# cardV3.net
KiCad netlist of a schematic drawn in EAGLE
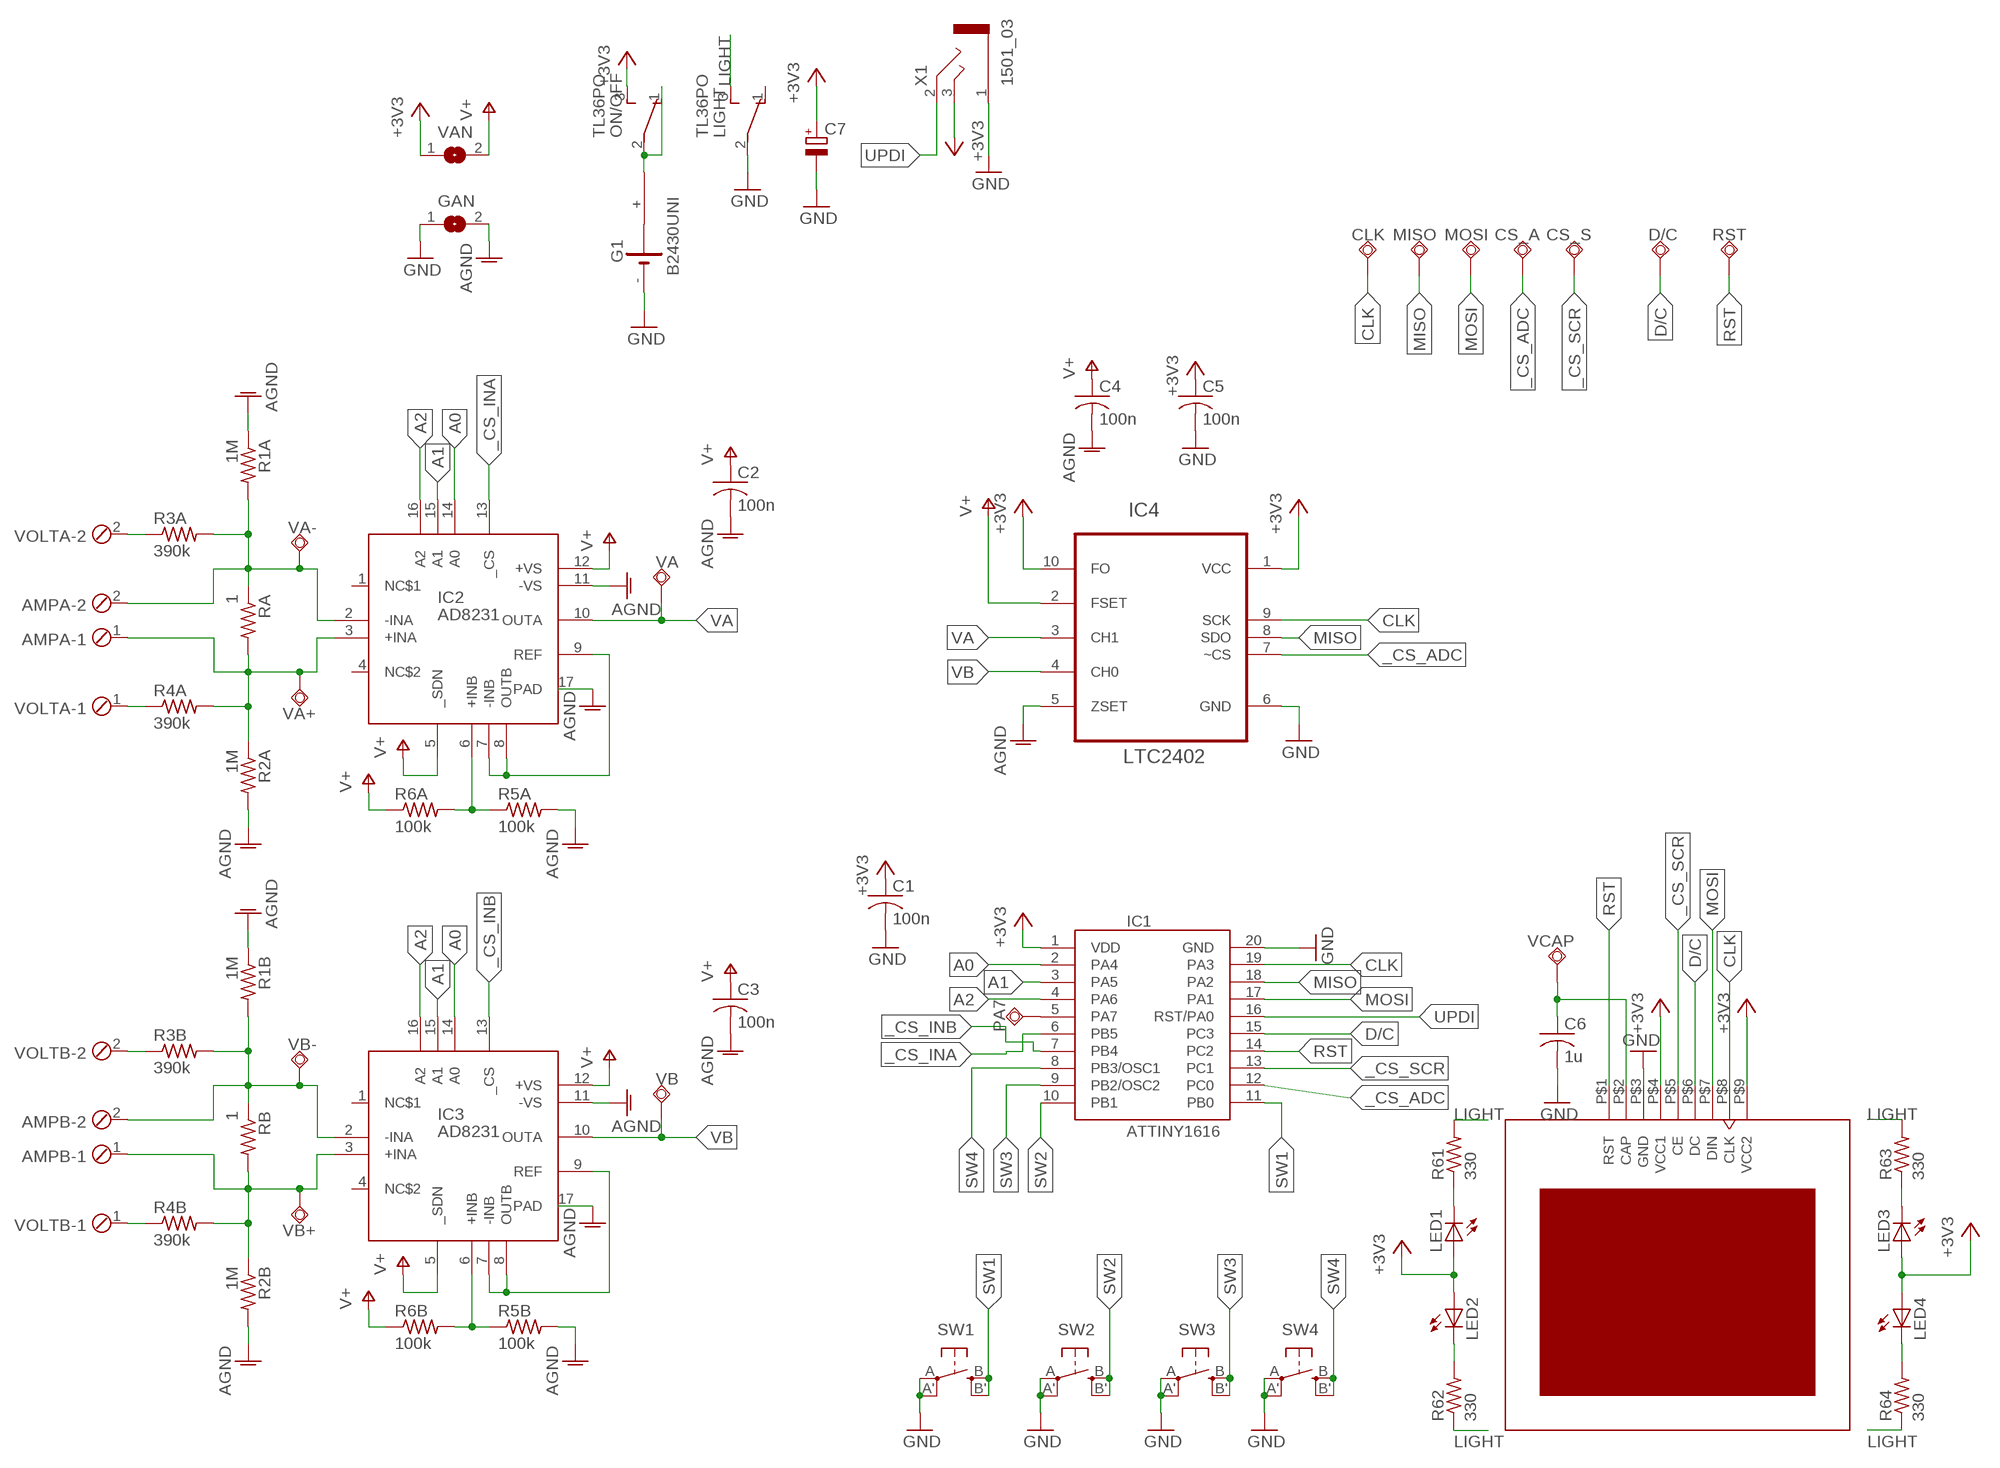
[diagram p0: schematic, sheet 1]

(export (version "E")
  (design (tool "Eeschema 10.0.6"))
  (components
    (comp (ref "AMPA")
      (value "MPT2")
      (footprint "eagle-import:2POL254")
      (libsource (lib "eagle-import") (part "MPT2"))
    )
    (comp (ref "AMPB")
      (value "MPT2")
      (footprint "eagle-import:2POL254")
      (libsource (lib "eagle-import") (part "MPT2"))
    )
    (comp (ref "C1")
      (value "100n")
      (footprint "eagle-import:C0805K")
      (libsource (lib "eagle-import") (part "C-USC0805K"))
    )
    (comp (ref "C2")
      (value "100n")
      (footprint "eagle-import:C0805K")
      (libsource (lib "eagle-import") (part "C-USC0805K"))
    )
    (comp (ref "C3")
      (value "100n")
      (footprint "eagle-import:C0805K")
      (libsource (lib "eagle-import") (part "C-USC0805K"))
    )
    (comp (ref "C4")
      (value "100n")
      (footprint "eagle-import:C0805K")
      (libsource (lib "eagle-import") (part "C-USC0805K"))
    )
    (comp (ref "C5")
      (value "100n")
      (footprint "eagle-import:C0805K")
      (libsource (lib "eagle-import") (part "C-USC0805K"))
    )
    (comp (ref "C6")
      (value "1u")
      (footprint "eagle-import:C0805")
      (libsource (lib "eagle-import") (part "resistor_C-USC0805"))
    )
    (comp (ref "C7")
      (value "CPOL-EU153CLV-0405")
      (footprint "eagle-import:153CLV-0405")
      (libsource (lib "eagle-import") (part "CPOL-EU153CLV-0405"))
    )
    (comp (ref "CLK")
      (value "TPSQB1,27")
      (footprint "eagle-import:B1,27")
      (libsource (lib "eagle-import") (part "TPSQB1,27"))
    )
    (comp (ref "CS_A")
      (value "TPSQB1,27")
      (footprint "eagle-import:B1,27")
      (libsource (lib "eagle-import") (part "TPSQB1,27"))
    )
    (comp (ref "CS_S")
      (value "TPSQB1,27")
      (footprint "eagle-import:B1,27")
      (libsource (lib "eagle-import") (part "TPSQB1,27"))
    )
    (comp (ref "D/C")
      (value "TPSQB1,27")
      (footprint "eagle-import:B1,27")
      (libsource (lib "eagle-import") (part "TPSQB1,27"))
    )
    (comp (ref "G1")
      (value "B2430UNI")
      (footprint "eagle-import:B2430UNI")
      (libsource (lib "eagle-import") (part "B2430UNI"))
    )
    (comp (ref "GAN") (value "SJ") (footprint "eagle-import:SJ") (libsource (lib "eagle-import") (part "SJ")))
    (comp (ref "IC1")
      (value "ATTINY1616")
      (footprint "eagle-import:SO20W")
      (libsource (lib "eagle-import") (part "ATTINY1616"))
    )
    (comp (ref "IC2")
      (value "AD8231")
      (footprint "eagle-import:LFCSP16")
      (libsource (lib "eagle-import") (part "AD8231"))
    )
    (comp (ref "IC3")
      (value "AD8231")
      (footprint "eagle-import:LFCSP16")
      (libsource (lib "eagle-import") (part "AD8231"))
    )
    (comp (ref "IC4")
      (value "LTC2402")
      (footprint "eagle-import:MSOP10")
      (libsource (lib "eagle-import") (part "LTC2402CMS"))
    )
    (comp (ref "LED1")
      (value "LEDCHIP-LED0805")
      (footprint "eagle-import:CHIP-LED0805")
      (libsource (lib "eagle-import") (part "LEDCHIP-LED0805"))
    )
    (comp (ref "LED2")
      (value "LEDCHIP-LED0805")
      (footprint "eagle-import:CHIP-LED0805")
      (libsource (lib "eagle-import") (part "LEDCHIP-LED0805"))
    )
    (comp (ref "LED3")
      (value "LEDCHIP-LED0805")
      (footprint "eagle-import:CHIP-LED0805")
      (libsource (lib "eagle-import") (part "LEDCHIP-LED0805"))
    )
    (comp (ref "LED4")
      (value "LEDCHIP-LED0805")
      (footprint "eagle-import:CHIP-LED0805")
      (libsource (lib "eagle-import") (part "LEDCHIP-LED0805"))
    )
    (comp (ref "LIGHT")
      (value "TL36PO")
      (footprint "eagle-import:TL3XPO")
      (libsource (lib "eagle-import") (part "TL36PO"))
    )
    (comp (ref "MISO")
      (value "TPSQB1,27")
      (footprint "eagle-import:B1,27")
      (libsource (lib "eagle-import") (part "TPSQB1,27"))
    )
    (comp (ref "MOSI")
      (value "TPSQB1,27")
      (footprint "eagle-import:B1,27")
      (libsource (lib "eagle-import") (part "TPSQB1,27"))
    )
    (comp (ref "ON/OFF")
      (value "TL36PO")
      (footprint "eagle-import:TL3XPO")
      (libsource (lib "eagle-import") (part "TL36PO"))
    )
    (comp (ref "PA7")
      (value "TPSQB1,27")
      (footprint "eagle-import:B1,27")
      (libsource (lib "eagle-import") (part "TPSQB1,27"))
    )
    (comp (ref "R1A")
      (value "1M")
      (footprint "eagle-import:M0805")
      (libsource (lib "eagle-import") (part "R-US_M0805"))
    )
    (comp (ref "R1B")
      (value "1M")
      (footprint "eagle-import:M0805")
      (libsource (lib "eagle-import") (part "R-US_M0805"))
    )
    (comp (ref "R2A")
      (value "1M")
      (footprint "eagle-import:M0805")
      (libsource (lib "eagle-import") (part "R-US_M0805"))
    )
    (comp (ref "R2B")
      (value "1M")
      (footprint "eagle-import:M0805")
      (libsource (lib "eagle-import") (part "R-US_M0805"))
    )
    (comp (ref "R3A")
      (value "390k")
      (footprint "eagle-import:M0805")
      (libsource (lib "eagle-import") (part "R-US_M0805"))
    )
    (comp (ref "R3B")
      (value "390k")
      (footprint "eagle-import:M0805")
      (libsource (lib "eagle-import") (part "R-US_M0805"))
    )
    (comp (ref "R4A")
      (value "390k")
      (footprint "eagle-import:M0805")
      (libsource (lib "eagle-import") (part "R-US_M0805"))
    )
    (comp (ref "R4B")
      (value "390k")
      (footprint "eagle-import:M0805")
      (libsource (lib "eagle-import") (part "R-US_M0805"))
    )
    (comp (ref "R5A")
      (value "100k")
      (footprint "eagle-import:M0805")
      (libsource (lib "eagle-import") (part "R-US_M0805"))
    )
    (comp (ref "R5B")
      (value "100k")
      (footprint "eagle-import:M0805")
      (libsource (lib "eagle-import") (part "R-US_M0805"))
    )
    (comp (ref "R6A")
      (value "100k")
      (footprint "eagle-import:M0805")
      (libsource (lib "eagle-import") (part "R-US_M0805"))
    )
    (comp (ref "R6B")
      (value "100k")
      (footprint "eagle-import:M0805")
      (libsource (lib "eagle-import") (part "R-US_M0805"))
    )
    (comp (ref "R61")
      (value "330")
      (footprint "eagle-import:M0805")
      (libsource (lib "eagle-import") (part "R-US_M0805"))
    )
    (comp (ref "R62")
      (value "330")
      (footprint "eagle-import:M0805")
      (libsource (lib "eagle-import") (part "R-US_M0805"))
    )
    (comp (ref "R63")
      (value "330")
      (footprint "eagle-import:M0805")
      (libsource (lib "eagle-import") (part "R-US_M0805"))
    )
    (comp (ref "R64")
      (value "330")
      (footprint "eagle-import:M0805")
      (libsource (lib "eagle-import") (part "R-US_M0805"))
    )
    (comp (ref "RA")
      (value "1")
      (footprint "eagle-import:M0805")
      (libsource (lib "eagle-import") (part "R-US_M0805"))
    )
    (comp (ref "RB")
      (value "1")
      (footprint "eagle-import:M0805")
      (libsource (lib "eagle-import") (part "R-US_M0805"))
    )
    (comp (ref "RST")
      (value "TPSQB1,27")
      (footprint "eagle-import:B1,27")
      (libsource (lib "eagle-import") (part "TPSQB1,27"))
    )
    (comp (ref "SCR")
      (value "NOKIA_SCREEN")
      (footprint "eagle-import:NOKIA_SCREEN")
      (libsource (lib "eagle-import") (part "NOKIA_SCREEN"))
    )
    (comp (ref "SW1")
      (value "SPST_TACT-EVQQ2")
      (footprint "eagle-import:EVQ-Q2")
      (libsource (lib "eagle-import") (part "SPST_TACT-EVQQ2"))
    )
    (comp (ref "SW2")
      (value "SPST_TACT-EVQQ2")
      (footprint "eagle-import:EVQ-Q2")
      (libsource (lib "eagle-import") (part "SPST_TACT-EVQQ2"))
    )
    (comp (ref "SW3")
      (value "SPST_TACT-EVQQ2")
      (footprint "eagle-import:EVQ-Q2")
      (libsource (lib "eagle-import") (part "SPST_TACT-EVQQ2"))
    )
    (comp (ref "SW4")
      (value "SPST_TACT-EVQQ2")
      (footprint "eagle-import:EVQ-Q2")
      (libsource (lib "eagle-import") (part "SPST_TACT-EVQQ2"))
    )
    (comp (ref "VA")
      (value "TPSQB1,27")
      (footprint "eagle-import:B1,27")
      (libsource (lib "eagle-import") (part "TPSQB1,27"))
    )
    (comp (ref "VA+")
      (value "TPSQB1,27")
      (footprint "eagle-import:B1,27")
      (libsource (lib "eagle-import") (part "TPSQB1,27"))
    )
    (comp (ref "VA-")
      (value "TPSQB1,27")
      (footprint "eagle-import:B1,27")
      (libsource (lib "eagle-import") (part "TPSQB1,27"))
    )
    (comp (ref "VAN") (value "SJ") (footprint "eagle-import:SJ") (libsource (lib "eagle-import") (part "SJ")))
    (comp (ref "VB")
      (value "TPSQB1,27")
      (footprint "eagle-import:B1,27")
      (libsource (lib "eagle-import") (part "TPSQB1,27"))
    )
    (comp (ref "VB+")
      (value "TPSQB1,27")
      (footprint "eagle-import:B1,27")
      (libsource (lib "eagle-import") (part "TPSQB1,27"))
    )
    (comp (ref "VB-")
      (value "TPSQB1,27")
      (footprint "eagle-import:B1,27")
      (libsource (lib "eagle-import") (part "TPSQB1,27"))
    )
    (comp (ref "VCAP")
      (value "TPSQB1,27")
      (footprint "eagle-import:B1,27")
      (libsource (lib "eagle-import") (part "TPSQB1,27"))
    )
    (comp (ref "VOLTA")
      (value "MPT2")
      (footprint "eagle-import:2POL254")
      (libsource (lib "eagle-import") (part "MPT2"))
    )
    (comp (ref "VOLTB")
      (value "MPT2")
      (footprint "eagle-import:2POL254")
      (libsource (lib "eagle-import") (part "MPT2"))
    )
    (comp (ref "X1")
      (value "1501_03")
      (footprint "eagle-import:1501_03")
      (libsource (lib "eagle-import") (part "1501_03"))
    )
  )
  (nets
    (net (code "1") (name "+3V3") (class "Default")
      (node (ref "C1") (pin "1") (pinfunction "1_1") (pintype "passive"))
      (node (ref "C5") (pin "1") (pinfunction "1_1") (pintype "passive"))
      (node (ref "C7") (pin "+") (pinfunction "+_+") (pintype "passive"))
      (node (ref "IC1") (pin "1") (pinfunction "VDD_1") (pintype "power_in"))
      (node (ref "IC4") (pin "1") (pinfunction "VCC_1") (pintype "power_in"))
      (node (ref "IC4") (pin "10") (pinfunction "FO_10") (pintype "input"))
      (node (ref "LED1") (pin "A") (pinfunction "A_A") (pintype "passive"))
      (node (ref "LED2") (pin "A") (pinfunction "A_A") (pintype "passive"))
      (node (ref "LED3") (pin "A") (pinfunction "A_A") (pintype "passive"))
      (node (ref "LED4") (pin "A") (pinfunction "A_A") (pintype "passive"))
      (node (ref "ON/OFF") (pin "3") (pinfunction "S_3") (pintype "passive"))
      (node (ref "SCR") (pin "P$4") (pinfunction "VCC1_P$4") (pintype "power_in"))
      (node (ref "SCR") (pin "P$9") (pinfunction "VCC2_P$9") (pintype "power_in"))
      (node (ref "VAN") (pin "1") (pinfunction "1_1") (pintype "passive"))
      (node (ref "X1") (pin "3") (pinfunction "3_3") (pintype "passive"))
    )
    (net (code "2") (name "/LIGHT") (class "Default")
      (node (ref "LIGHT") (pin "3") (pinfunction "S_3") (pintype "passive"))
      (node (ref "R61") (pin "2") (pinfunction "2_2") (pintype "passive"))
      (node (ref "R62") (pin "1") (pinfunction "1_1") (pintype "passive"))
      (node (ref "R63") (pin "2") (pinfunction "2_2") (pintype "passive"))
      (node (ref "R64") (pin "1") (pinfunction "1_1") (pintype "passive"))
    )
    (net (code "3") (name "A0") (class "Default")
      (node (ref "IC1") (pin "2") (pinfunction "PA4_2") (pintype "bidirectional"))
      (node (ref "IC2") (pin "14") (pinfunction "A0_14") (pintype "input"))
      (node (ref "IC3") (pin "14") (pinfunction "A0_14") (pintype "input"))
    )
    (net (code "4") (name "A1") (class "Default")
      (node (ref "IC1") (pin "3") (pinfunction "PA5_3") (pintype "bidirectional"))
      (node (ref "IC2") (pin "15") (pinfunction "A1_15") (pintype "input"))
      (node (ref "IC3") (pin "15") (pinfunction "A1_15") (pintype "input"))
    )
    (net (code "5") (name "A2") (class "Default")
      (node (ref "IC1") (pin "4") (pinfunction "PA6_4") (pintype "bidirectional"))
      (node (ref "IC2") (pin "16") (pinfunction "A2_16") (pintype "input"))
      (node (ref "IC3") (pin "16") (pinfunction "A2_16") (pintype "input"))
    )
    (net (code "6") (name "AGND") (class "Default")
      (node (ref "C2") (pin "2") (pinfunction "2_2") (pintype "passive"))
      (node (ref "C3") (pin "2") (pinfunction "2_2") (pintype "passive"))
      (node (ref "C4") (pin "2") (pinfunction "2_2") (pintype "passive"))
      (node (ref "GAN") (pin "2") (pinfunction "2_2") (pintype "passive"))
      (node (ref "IC2") (pin "11") (pinfunction "-VS_11") (pintype "power_in"))
      (node (ref "IC2") (pin "17") (pinfunction "PAD_17") (pintype "power_in"))
      (node (ref "IC3") (pin "11") (pinfunction "-VS_11") (pintype "power_in"))
      (node (ref "IC3") (pin "17") (pinfunction "PAD_17") (pintype "power_in"))
      (node (ref "IC4") (pin "5") (pinfunction "ZSET_5") (pintype "input"))
      (node (ref "R1A") (pin "1") (pinfunction "1_1") (pintype "passive"))
      (node (ref "R1B") (pin "1") (pinfunction "1_1") (pintype "passive"))
      (node (ref "R2A") (pin "2") (pinfunction "2_2") (pintype "passive"))
      (node (ref "R2B") (pin "2") (pinfunction "2_2") (pintype "passive"))
      (node (ref "R5A") (pin "2") (pinfunction "2_2") (pintype "passive"))
      (node (ref "R5B") (pin "2") (pinfunction "2_2") (pintype "passive"))
    )
    (net (code "7") (name "CLK") (class "Default")
      (node (ref "CLK") (pin "TP") (pinfunction "TP_TP") (pintype "input"))
      (node (ref "IC1") (pin "19") (pinfunction "PA3_19") (pintype "bidirectional"))
      (node (ref "IC4") (pin "9") (pinfunction "SCK_9") (pintype "input"))
      (node (ref "SCR") (pin "P$8") (pinfunction "CLK_P$8") (pintype "input"))
    )
    (net (code "8") (name "D{slash}C") (class "Default")
      (node (ref "D/C") (pin "TP") (pinfunction "TP_TP") (pintype "input"))
      (node (ref "IC1") (pin "15") (pinfunction "PC3_15") (pintype "bidirectional"))
      (node (ref "SCR") (pin "P$6") (pinfunction "DC_P$6") (pintype "input"))
    )
    (net (code "9") (name "GND") (class "Default")
      (node (ref "C1") (pin "2") (pinfunction "2_2") (pintype "passive"))
      (node (ref "C5") (pin "2") (pinfunction "2_2") (pintype "passive"))
      (node (ref "C6") (pin "2") (pinfunction "2_2") (pintype "passive"))
      (node (ref "C7") (pin "-") (pinfunction "-_-") (pintype "passive"))
      (node (ref "G1") (pin "-") (pinfunction "-_-") (pintype "passive"))
      (node (ref "GAN") (pin "1") (pinfunction "1_1") (pintype "passive"))
      (node (ref "IC1") (pin "20") (pinfunction "GND_20") (pintype "power_in"))
      (node (ref "IC4") (pin "6") (pinfunction "GND_6") (pintype "passive"))
      (node (ref "LIGHT") (pin "2") (pinfunction "P_2") (pintype "passive"))
      (node (ref "SCR") (pin "P$3") (pinfunction "GND_P$3") (pintype "power_in"))
      (node (ref "SW1") (pin "A") (pinfunction "P_A") (pintype "passive"))
      (node (ref "SW1") (pin "A'") (pinfunction "P1_A'") (pintype "passive"))
      (node (ref "SW2") (pin "A") (pinfunction "P_A") (pintype "passive"))
      (node (ref "SW2") (pin "A'") (pinfunction "P1_A'") (pintype "passive"))
      (node (ref "SW3") (pin "A") (pinfunction "P_A") (pintype "passive"))
      (node (ref "SW3") (pin "A'") (pinfunction "P1_A'") (pintype "passive"))
      (node (ref "SW4") (pin "A") (pinfunction "P_A") (pintype "passive"))
      (node (ref "SW4") (pin "A'") (pinfunction "P1_A'") (pintype "passive"))
      (node (ref "X1") (pin "1") (pinfunction "1_1") (pintype "passive"))
    )
    (net (code "10") (name "MISO") (class "Default")
      (node (ref "IC1") (pin "18") (pinfunction "PA2_18") (pintype "bidirectional"))
      (node (ref "IC4") (pin "8") (pinfunction "SDO_8") (pintype "output"))
      (node (ref "MISO") (pin "TP") (pinfunction "TP_TP") (pintype "input"))
    )
    (net (code "11") (name "MOSI") (class "Default")
      (node (ref "IC1") (pin "17") (pinfunction "PA1_17") (pintype "bidirectional"))
      (node (ref "MOSI") (pin "TP") (pinfunction "TP_TP") (pintype "input"))
      (node (ref "SCR") (pin "P$7") (pinfunction "DIN_P$7") (pintype "input"))
    )
    (net (code "12") (name "Net-(AMPAB-1)") (class "Default")
      (node (ref "AMPA") (pin "2") (pinfunction "1_2") (pintype "passive"))
      (node (ref "IC2") (pin "2") (pinfunction "-INA_2") (pintype "input"))
      (node (ref "R1A") (pin "2") (pinfunction "2_2") (pintype "passive"))
      (node (ref "R3A") (pin "2") (pinfunction "2_2") (pintype "passive"))
      (node (ref "RA") (pin "1") (pinfunction "1_1") (pintype "passive"))
      (node (ref "VA-") (pin "TP") (pinfunction "TP_TP") (pintype "input"))
    )
    (net (code "13") (name "Net-(AMPBB-1)") (class "Default")
      (node (ref "AMPB") (pin "2") (pinfunction "1_2") (pintype "passive"))
      (node (ref "IC3") (pin "2") (pinfunction "-INA_2") (pintype "input"))
      (node (ref "R1B") (pin "2") (pinfunction "2_2") (pintype "passive"))
      (node (ref "R3B") (pin "2") (pinfunction "2_2") (pintype "passive"))
      (node (ref "RB") (pin "1") (pinfunction "1_1") (pintype "passive"))
      (node (ref "VB-") (pin "TP") (pinfunction "TP_TP") (pintype "input"))
    )
    (net (code "14") (name "Net-(IC1-PA7)") (class "Default")
      (node (ref "IC1") (pin "5") (pinfunction "PA7_5") (pintype "bidirectional"))
      (node (ref "PA7") (pin "TP") (pinfunction "TP_TP") (pintype "input"))
    )
    (net (code "15") (name "Net-(IC2-+INA)") (class "Default")
      (node (ref "AMPA") (pin "1") (pinfunction "1_1") (pintype "passive"))
      (node (ref "IC2") (pin "3") (pinfunction "+INA_3") (pintype "input"))
      (node (ref "R2A") (pin "1") (pinfunction "1_1") (pintype "passive"))
      (node (ref "R4A") (pin "2") (pinfunction "2_2") (pintype "passive"))
      (node (ref "RA") (pin "2") (pinfunction "2_2") (pintype "passive"))
      (node (ref "VA+") (pin "TP") (pinfunction "TP_TP") (pintype "input"))
    )
    (net (code "16") (name "Net-(IC2-+INB)") (class "Default")
      (node (ref "IC2") (pin "6") (pinfunction "+INB_6") (pintype "input"))
      (node (ref "R5A") (pin "1") (pinfunction "1_1") (pintype "passive"))
      (node (ref "R6A") (pin "2") (pinfunction "2_2") (pintype "passive"))
    )
    (net (code "17") (name "Net-(IC2--INB)") (class "Default")
      (node (ref "IC2") (pin "7") (pinfunction "-INB_7") (pintype "input"))
      (node (ref "IC2") (pin "8") (pinfunction "OUTB_8") (pintype "output"))
      (node (ref "IC2") (pin "9") (pinfunction "REF_9") (pintype "input"))
    )
    (net (code "18") (name "Net-(IC3-+INA)") (class "Default")
      (node (ref "AMPB") (pin "1") (pinfunction "1_1") (pintype "passive"))
      (node (ref "IC3") (pin "3") (pinfunction "+INA_3") (pintype "input"))
      (node (ref "R2B") (pin "1") (pinfunction "1_1") (pintype "passive"))
      (node (ref "R4B") (pin "2") (pinfunction "2_2") (pintype "passive"))
      (node (ref "RB") (pin "2") (pinfunction "2_2") (pintype "passive"))
      (node (ref "VB+") (pin "TP") (pinfunction "TP_TP") (pintype "input"))
    )
    (net (code "19") (name "Net-(IC3-+INB)") (class "Default")
      (node (ref "IC3") (pin "6") (pinfunction "+INB_6") (pintype "input"))
      (node (ref "R5B") (pin "1") (pinfunction "1_1") (pintype "passive"))
      (node (ref "R6B") (pin "2") (pinfunction "2_2") (pintype "passive"))
    )
    (net (code "20") (name "Net-(IC3--INB)") (class "Default")
      (node (ref "IC3") (pin "7") (pinfunction "-INB_7") (pintype "input"))
      (node (ref "IC3") (pin "8") (pinfunction "OUTB_8") (pintype "output"))
      (node (ref "IC3") (pin "9") (pinfunction "REF_9") (pintype "input"))
    )
    (net (code "21") (name "Net-(LED1-PadC)") (class "Default")
      (node (ref "LED1") (pin "C") (pinfunction "C_C") (pintype "passive"))
      (node (ref "R61") (pin "1") (pinfunction "1_1") (pintype "passive"))
    )
    (net (code "22") (name "Net-(LED2-PadC)") (class "Default")
      (node (ref "LED2") (pin "C") (pinfunction "C_C") (pintype "passive"))
      (node (ref "R62") (pin "2") (pinfunction "2_2") (pintype "passive"))
    )
    (net (code "23") (name "Net-(LED3-PadC)") (class "Default")
      (node (ref "LED3") (pin "C") (pinfunction "C_C") (pintype "passive"))
      (node (ref "R63") (pin "1") (pinfunction "1_1") (pintype "passive"))
    )
    (net (code "24") (name "Net-(LED4-PadC)") (class "Default")
      (node (ref "LED4") (pin "C") (pinfunction "C_C") (pintype "passive"))
      (node (ref "R64") (pin "2") (pinfunction "2_2") (pintype "passive"))
    )
    (net (code "25") (name "Net-(ON/OFF-O)") (class "Default")
      (node (ref "G1") (pin "+") (pinfunction "+_+") (pintype "passive"))
      (node (ref "ON/OFF") (pin "1") (pinfunction "O_1") (pintype "passive"))
      (node (ref "ON/OFF") (pin "2") (pinfunction "P_2") (pintype "passive"))
    )
    (net (code "26") (name "Net-(R4A-Pad1)") (class "Default")
      (node (ref "R4A") (pin "1") (pinfunction "1_1") (pintype "passive"))
      (node (ref "VOLTA") (pin "1") (pinfunction "1_1") (pintype "passive"))
    )
    (net (code "27") (name "Net-(R4B-Pad1)") (class "Default")
      (node (ref "R4B") (pin "1") (pinfunction "1_1") (pintype "passive"))
      (node (ref "VOLTB") (pin "1") (pinfunction "1_1") (pintype "passive"))
    )
    (net (code "28") (name "Net-(SCR-CAP)") (class "Default")
      (node (ref "C6") (pin "1") (pinfunction "1_1") (pintype "passive"))
      (node (ref "SCR") (pin "P$2") (pinfunction "CAP_P$2") (pintype "passive"))
      (node (ref "VCAP") (pin "TP") (pinfunction "TP_TP") (pintype "input"))
    )
    (net (code "29") (name "Net-(VOLTAB-1)") (class "Default")
      (node (ref "R3A") (pin "1") (pinfunction "1_1") (pintype "passive"))
      (node (ref "VOLTA") (pin "2") (pinfunction "1_2") (pintype "passive"))
    )
    (net (code "30") (name "Net-(VOLTBB-1)") (class "Default")
      (node (ref "R3B") (pin "1") (pinfunction "1_1") (pintype "passive"))
      (node (ref "VOLTB") (pin "2") (pinfunction "1_2") (pintype "passive"))
    )
    (net (code "31") (name "RST") (class "Default")
      (node (ref "IC1") (pin "14") (pinfunction "PC2_14") (pintype "bidirectional"))
      (node (ref "RST") (pin "TP") (pinfunction "TP_TP") (pintype "input"))
      (node (ref "SCR") (pin "P$1") (pinfunction "RST_P$1") (pintype "input"))
    )
    (net (code "32") (name "SW1") (class "Default")
      (node (ref "IC1") (pin "11") (pinfunction "PB0_11") (pintype "bidirectional"))
      (node (ref "SW1") (pin "B") (pinfunction "S_B") (pintype "passive"))
      (node (ref "SW1") (pin "B'") (pinfunction "S1_B'") (pintype "passive"))
    )
    (net (code "33") (name "SW2") (class "Default")
      (node (ref "IC1") (pin "10") (pinfunction "PB1_10") (pintype "bidirectional"))
      (node (ref "SW2") (pin "B") (pinfunction "S_B") (pintype "passive"))
      (node (ref "SW2") (pin "B'") (pinfunction "S1_B'") (pintype "passive"))
    )
    (net (code "34") (name "SW3") (class "Default")
      (node (ref "IC1") (pin "9") (pinfunction "PB2/OSC2_9") (pintype "bidirectional"))
      (node (ref "SW3") (pin "B") (pinfunction "S_B") (pintype "passive"))
      (node (ref "SW3") (pin "B'") (pinfunction "S1_B'") (pintype "passive"))
    )
    (net (code "35") (name "SW4") (class "Default")
      (node (ref "IC1") (pin "8") (pinfunction "PB3/OSC1_8") (pintype "bidirectional"))
      (node (ref "SW4") (pin "B") (pinfunction "S_B") (pintype "passive"))
      (node (ref "SW4") (pin "B'") (pinfunction "S1_B'") (pintype "passive"))
    )
    (net (code "36") (name "UPDI") (class "Default")
      (node (ref "IC1") (pin "16") (pinfunction "RST/PA0_16") (pintype "bidirectional"))
      (node (ref "X1") (pin "2") (pinfunction "2_2") (pintype "passive"))
    )
    (net (code "37") (name "V+") (class "Default")
      (node (ref "C2") (pin "1") (pinfunction "1_1") (pintype "passive"))
      (node (ref "C3") (pin "1") (pinfunction "1_1") (pintype "passive"))
      (node (ref "C4") (pin "1") (pinfunction "1_1") (pintype "passive"))
      (node (ref "IC2") (pin "12") (pinfunction "+VS_12") (pintype "power_in"))
      (node (ref "IC2") (pin "5") (pinfunction "_SDN_5") (pintype "input"))
      (node (ref "IC3") (pin "12") (pinfunction "+VS_12") (pintype "power_in"))
      (node (ref "IC3") (pin "5") (pinfunction "_SDN_5") (pintype "input"))
      (node (ref "IC4") (pin "2") (pinfunction "FSET_2") (pintype "input"))
      (node (ref "R6A") (pin "1") (pinfunction "1_1") (pintype "passive"))
      (node (ref "R6B") (pin "1") (pinfunction "1_1") (pintype "passive"))
      (node (ref "VAN") (pin "2") (pinfunction "2_2") (pintype "passive"))
    )
    (net (code "38") (name "VA") (class "Default")
      (node (ref "IC2") (pin "10") (pinfunction "OUTA_10") (pintype "output"))
      (node (ref "IC4") (pin "3") (pinfunction "CH1_3") (pintype "input"))
      (node (ref "VA") (pin "TP") (pinfunction "TP_TP") (pintype "input"))
    )
    (net (code "39") (name "VB") (class "Default")
      (node (ref "IC3") (pin "10") (pinfunction "OUTA_10") (pintype "output"))
      (node (ref "IC4") (pin "4") (pinfunction "CH0_4") (pintype "input"))
      (node (ref "VB") (pin "TP") (pinfunction "TP_TP") (pintype "input"))
    )
    (net (code "40") (name "_CS_ADC") (class "Default")
      (node (ref "CS_A") (pin "TP") (pinfunction "TP_TP") (pintype "input"))
      (node (ref "IC1") (pin "12") (pinfunction "PC0_12") (pintype "bidirectional"))
      (node (ref "IC4") (pin "7") (pinfunction "~{CS}_7") (pintype "input"))
    )
    (net (code "41") (name "_CS_INA") (class "Default")
      (node (ref "IC1") (pin "6") (pinfunction "PB5_6") (pintype "bidirectional"))
      (node (ref "IC2") (pin "13") (pinfunction "_CS_13") (pintype "input"))
    )
    (net (code "42") (name "_CS_INB") (class "Default")
      (node (ref "IC1") (pin "7") (pinfunction "PB4_7") (pintype "bidirectional"))
      (node (ref "IC3") (pin "13") (pinfunction "_CS_13") (pintype "input"))
    )
    (net (code "43") (name "_CS_SCR") (class "Default")
      (node (ref "CS_S") (pin "TP") (pinfunction "TP_TP") (pintype "input"))
      (node (ref "IC1") (pin "13") (pinfunction "PC1_13") (pintype "bidirectional"))
      (node (ref "SCR") (pin "P$5") (pinfunction "CE_P$5") (pintype "input"))
    )
    (net (code "44") (name "unconnected-(G1-+-Pad+@1)") (class "Default")
      (node (ref "G1") (pin "+@1") (pinfunction "+_+@1") (pintype "passive"))
    )
    (net (code "45") (name "unconnected-(G1-+-Pad+@2)") (class "Default")
      (node (ref "G1") (pin "+@2") (pinfunction "+_+@2") (pintype "passive"))
    )
    (net (code "46") (name "unconnected-(G1-+-Pad+@3)") (class "Default")
      (node (ref "G1") (pin "+@3") (pinfunction "+_+@3") (pintype "passive"))
    )
    (net (code "47") (name "unconnected-(G1-+-Pad+@4)") (class "Default")
      (node (ref "G1") (pin "+@4") (pinfunction "+_+@4") (pintype "passive"))
    )
    (net (code "48") (name "unconnected-(G1---Pad-@1)") (class "Default")
      (node (ref "G1") (pin "-@1") (pinfunction "-_-@1") (pintype "passive"))
    )
    (net (code "49") (name "unconnected-(IC2-NC$1-Pad1)") (class "Default")
      (node (ref "IC2") (pin "1") (pinfunction "NC$1_1") (pintype "no_connect"))
    )
    (net (code "50") (name "unconnected-(IC2-NC$2-Pad4)") (class "Default")
      (node (ref "IC2") (pin "4") (pinfunction "NC$2_4") (pintype "no_connect"))
    )
    (net (code "51") (name "unconnected-(IC3-NC$1-Pad1)") (class "Default")
      (node (ref "IC3") (pin "1") (pinfunction "NC$1_1") (pintype "no_connect"))
    )
    (net (code "52") (name "unconnected-(IC3-NC$2-Pad4)") (class "Default")
      (node (ref "IC3") (pin "4") (pinfunction "NC$2_4") (pintype "no_connect"))
    )
    (net (code "53") (name "unconnected-(LIGHT-O-Pad1)") (class "Default")
      (node (ref "LIGHT") (pin "1") (pinfunction "O_1") (pintype "passive"))
    )
  )
)
